# TUEV071.net
KiCad netlist of a schematic drawn in EAGLE
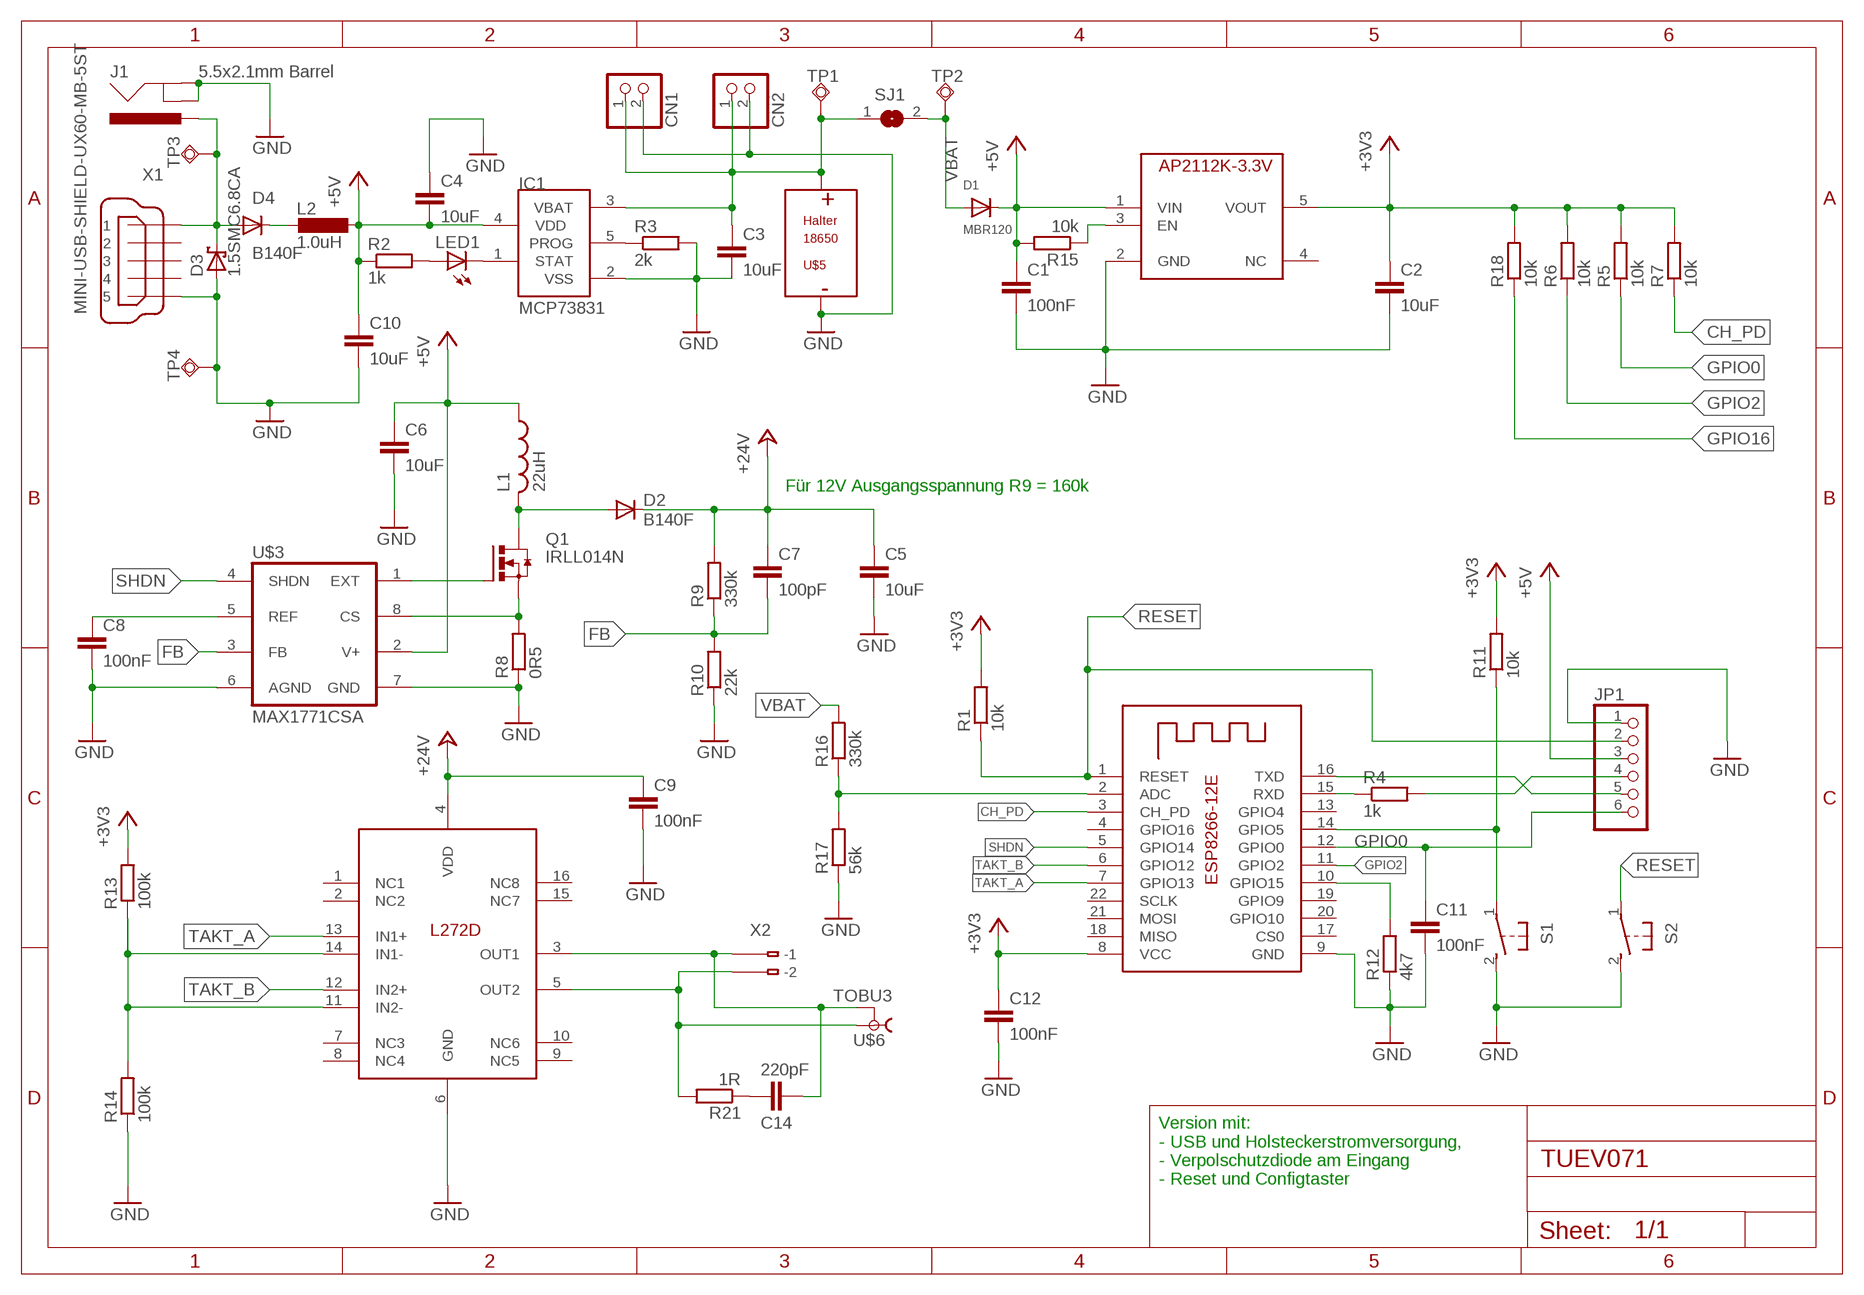
[diagram p0: schematic, sheet 1]

(export (version "E")
  (design (tool "Eeschema 10.0.6"))
  (components
    (comp (ref "C1")
      (value "100nF")
      (footprint "eagle-import:C0603K")
      (libsource (lib "eagle-import") (part "C-EUC0603K"))
    )
    (comp (ref "C2")
      (value "10uF")
      (footprint "eagle-import:C0603K")
      (libsource (lib "eagle-import") (part "C-EUC0603K"))
    )
    (comp (ref "C3")
      (value "10uF")
      (footprint "eagle-import:C0603K")
      (libsource (lib "eagle-import") (part "C-EUC0603K"))
    )
    (comp (ref "C4")
      (value "10uF")
      (footprint "eagle-import:C0603K")
      (libsource (lib "eagle-import") (part "C-EUC0603K"))
    )
    (comp (ref "C5")
      (value "10uF")
      (footprint "eagle-import:C1210K")
      (libsource (lib "eagle-import") (part "C-EUC1210K"))
    )
    (comp (ref "C6")
      (value "10uF")
      (footprint "eagle-import:C0603K")
      (libsource (lib "eagle-import") (part "C-EUC0603K"))
    )
    (comp (ref "C7")
      (value "100pF")
      (footprint "eagle-import:C0603K")
      (libsource (lib "eagle-import") (part "C-EUC0603K"))
    )
    (comp (ref "C8")
      (value "100nF")
      (footprint "eagle-import:C0603K")
      (libsource (lib "eagle-import") (part "C-EUC0603K"))
    )
    (comp (ref "C9")
      (value "100nF")
      (footprint "eagle-import:C0603K")
      (libsource (lib "eagle-import") (part "C-EUC0603K"))
    )
    (comp (ref "C10")
      (value "10uF")
      (footprint "eagle-import:C0603K")
      (libsource (lib "eagle-import") (part "C-EUC0603K"))
    )
    (comp (ref "C11")
      (value "100nF")
      (footprint "eagle-import:C0603K")
      (libsource (lib "eagle-import") (part "C-EUC0603K"))
    )
    (comp (ref "C12")
      (value "100nF")
      (footprint "eagle-import:C0603K")
      (libsource (lib "eagle-import") (part "C-EUC0603K"))
    )
    (comp (ref "C14")
      (value "220pF")
      (footprint "eagle-import:C0603K")
      (libsource (lib "eagle-import") (part "C-EUC0603K"))
    )
    (comp (ref "CN1")
      (value "JST_2PIN-SMT-RA")
      (footprint "eagle-import:JST-PH-2-SMT-RA")
      (libsource (lib "eagle-import") (part "JST_2PIN-SMT-RA"))
    )
    (comp (ref "CN2")
      (value "JST_2PIN-SMT-RA")
      (footprint "eagle-import:JST-PH-2-SMT-RA")
      (libsource (lib "eagle-import") (part "JST_2PIN-SMT-RA"))
    )
    (comp (ref "D1")
      (value "MBR120")
      (footprint "eagle-import:SOD-123")
      (libsource (lib "eagle-import") (part "DIODESOD-123"))
    )
    (comp (ref "D2")
      (value "B140F")
      (footprint "eagle-import:DO214AC")
      (libsource (lib "eagle-import") (part "DIODE-DO214AC"))
    )
    (comp (ref "D3")
      (value "1.5SMC6.8CA")
      (footprint "eagle-import:SMC")
      (libsource (lib "eagle-import") (part "SCHOTTKY-DIODESMC"))
    )
    (comp (ref "D4")
      (value "B140F")
      (footprint "eagle-import:DO214AC")
      (libsource (lib "eagle-import") (part "DIODE-DO214AC"))
    )
    (comp (ref "IC1")
      (value "MCP73831")
      (footprint "eagle-import:SOT23-5L")
      (libsource (lib "eagle-import") (part "MCP73831"))
    )
    (comp (ref "J1")
      (value "5.5x2.1mm Barrel")
      (footprint "eagle-import:POWER_JACK_SMD")
      (libsource (lib "eagle-import") (part "POWER_JACKSMD"))
    )
    (comp (ref "JP1")
      (value "PINHD-1X6")
      (footprint "eagle-import:1X06")
      (libsource (lib "eagle-import") (part "PINHD-1X6"))
    )
    (comp (ref "L1")
      (value "22uH")
      (footprint "eagle-import:L5650M")
      (libsource (lib "eagle-import") (part "L-USL5650M"))
    )
    (comp (ref "L2")
      (value "1.0uH")
      (footprint "eagle-import:L3230M")
      (libsource (lib "eagle-import") (part "L-EUL3230M"))
    )
    (comp (ref "LED1")
      (value "LEDCHIPLED_0805")
      (footprint "eagle-import:CHIPLED_0805")
      (libsource (lib "eagle-import") (part "LEDCHIPLED_0805"))
    )
    (comp (ref "Q1")
      (value "IRLL014N")
      (footprint "eagle-import:SOT223")
      (libsource (lib "eagle-import") (part "N-HEXFET-2D_?-SOT232IRLL014N"))
    )
    (comp (ref "R1")
      (value "10k")
      (footprint "eagle-import:M1206")
      (libsource (lib "eagle-import") (part "R-EU_M1206"))
    )
    (comp (ref "R2")
      (value "1k")
      (footprint "eagle-import:M1206")
      (libsource (lib "eagle-import") (part "R-EU_M1206"))
    )
    (comp (ref "R3")
      (value "2k")
      (footprint "eagle-import:M1206")
      (libsource (lib "eagle-import") (part "R-EU_M1206"))
    )
    (comp (ref "R4")
      (value "1k")
      (footprint "eagle-import:M1206")
      (libsource (lib "eagle-import") (part "R-EU_M1206"))
    )
    (comp (ref "R5")
      (value "10k")
      (footprint "eagle-import:M1206")
      (libsource (lib "eagle-import") (part "R-EU_M1206"))
    )
    (comp (ref "R6")
      (value "10k")
      (footprint "eagle-import:M1206")
      (libsource (lib "eagle-import") (part "R-EU_M1206"))
    )
    (comp (ref "R7")
      (value "10k")
      (footprint "eagle-import:M1206")
      (libsource (lib "eagle-import") (part "R-EU_M1206"))
    )
    (comp (ref "R8")
      (value "0R5")
      (footprint "eagle-import:R2512")
      (libsource (lib "eagle-import") (part "R-EU_R2512"))
    )
    (comp (ref "R9")
      (value "330k")
      (footprint "eagle-import:M1206")
      (libsource (lib "eagle-import") (part "R-EU_M1206"))
    )
    (comp (ref "R10")
      (value "22k")
      (footprint "eagle-import:M1206")
      (libsource (lib "eagle-import") (part "R-EU_M1206"))
    )
    (comp (ref "R11")
      (value "10k")
      (footprint "eagle-import:M1206")
      (libsource (lib "eagle-import") (part "R-EU_M1206"))
    )
    (comp (ref "R12")
      (value "4k7")
      (footprint "eagle-import:M1206")
      (libsource (lib "eagle-import") (part "R-EU_M1206"))
    )
    (comp (ref "R13")
      (value "100k")
      (footprint "eagle-import:M1206")
      (libsource (lib "eagle-import") (part "R-EU_M1206"))
    )
    (comp (ref "R14")
      (value "100k")
      (footprint "eagle-import:M1206")
      (libsource (lib "eagle-import") (part "R-EU_M1206"))
    )
    (comp (ref "R15")
      (value "10k")
      (footprint "eagle-import:M1206")
      (libsource (lib "eagle-import") (part "R-EU_M1206"))
    )
    (comp (ref "R16")
      (value "330k")
      (footprint "eagle-import:M1206")
      (libsource (lib "eagle-import") (part "R-EU_M1206"))
    )
    (comp (ref "R17")
      (value "56k")
      (footprint "eagle-import:M1206")
      (libsource (lib "eagle-import") (part "R-EU_M1206"))
    )
    (comp (ref "R18")
      (value "10k")
      (footprint "eagle-import:M1206")
      (libsource (lib "eagle-import") (part "R-EU_M1206"))
    )
    (comp (ref "R21")
      (value "1R")
      (footprint "eagle-import:M1206")
      (libsource (lib "eagle-import") (part "R-EU_M1206"))
    )
    (comp (ref "S1")
      (value "31-XX")
      (footprint "eagle-import:B3F-31XX")
      (fields (field (name "MPN") "B3F-3100"))
      (libsource (lib "eagle-import") (part "31-XX"))
    )
    (comp (ref "S2")
      (value "31-XX")
      (footprint "eagle-import:B3F-31XX")
      (fields (field (name "MPN") "B3F-3100"))
      (libsource (lib "eagle-import") (part "31-XX"))
    )
    (comp (ref "SJ1") (value "SJ") (footprint "eagle-import:SJ") (libsource (lib "eagle-import") (part "SJ")))
    (comp (ref "TP1")
      (value "TPSQPAD1-13Y")
      (footprint "eagle-import:P1-13Y")
      (libsource (lib "eagle-import") (part "TPSQPAD1-13Y"))
    )
    (comp (ref "TP2")
      (value "TPSQPAD1-13Y")
      (footprint "eagle-import:P1-13Y")
      (libsource (lib "eagle-import") (part "TPSQPAD1-13Y"))
    )
    (comp (ref "TP3")
      (value "TPSQPAD1-13Y")
      (footprint "eagle-import:P1-13Y")
      (libsource (lib "eagle-import") (part "TPSQPAD1-13Y"))
    )
    (comp (ref "TP4")
      (value "TPSQPAD1-13Y")
      (footprint "eagle-import:P1-13Y")
      (libsource (lib "eagle-import") (part "TPSQPAD1-13Y"))
    )
    (comp (ref "U$1")
      (value "AP2112-3.3")
      (footprint "eagle-import:SOT23-5L")
      (libsource (lib "eagle-import") (part "AP2112-3.3"))
    )
    (comp (ref "U$2")
      (value "L272D")
      (footprint "eagle-import:SO16")
      (libsource (lib "eagle-import") (part "L272D"))
    )
    (comp (ref "U$3")
      (value "MAX1771CSA")
      (footprint "eagle-import:SO08")
      (libsource (lib "eagle-import") (part "MAX1771CSA"))
    )
    (comp (ref "U$4")
      (value "ESP-12E")
      (footprint "eagle-import:ESP-12E")
      (libsource (lib "eagle-import") (part "ESP-12E"))
    )
    (comp (ref "U$5")
      (value "HA1X18650SMD")
      (footprint "eagle-import:HA1X18650SMD")
      (libsource (lib "eagle-import") (part "HA1X18650SMD"))
    )
    (comp (ref "U$6")
      (value "TOBU3")
      (footprint "eagle-import:TOBU3-REICHELT")
      (libsource (lib "eagle-import") (part "TOBU3-REICHELT"))
    )
    (comp (ref "X1")
      (value "MINI-USB-SHIELD-UX60-MB-5ST")
      (footprint "eagle-import:UX60-MB-5ST")
      (libsource (lib "eagle-import") (part "MINI-USB-SHIELD-UX60-MB-5ST"))
    )
    (comp (ref "X2")
      (value "233-102")
      (footprint "eagle-import:233-102")
      (libsource (lib "eagle-import") (part "233-102"))
    )
  )
  (nets
    (net (code "1") (name "+3V3") (class "Default")
      (node (ref "C12") (pin "1") (pinfunction "1_1") (pintype "passive"))
      (node (ref "C2") (pin "1") (pinfunction "1_1") (pintype "passive"))
      (node (ref "R1") (pin "2") (pinfunction "2_2") (pintype "passive"))
      (node (ref "R11") (pin "2") (pinfunction "2_2") (pintype "passive"))
      (node (ref "R13") (pin "2") (pinfunction "2_2") (pintype "passive"))
      (node (ref "R18") (pin "2") (pinfunction "2_2") (pintype "passive"))
      (node (ref "R5") (pin "2") (pinfunction "2_2") (pintype "passive"))
      (node (ref "R6") (pin "2") (pinfunction "2_2") (pintype "passive"))
      (node (ref "R7") (pin "2") (pinfunction "2_2") (pintype "passive"))
      (node (ref "U$1") (pin "5") (pinfunction "VOUT_5") (pintype "power_in"))
      (node (ref "U$4") (pin "8") (pinfunction "VCC_8") (pintype "power_in"))
    )
    (net (code "2") (name "+5V") (class "Default")
      (node (ref "C1") (pin "1") (pinfunction "1_1") (pintype "passive"))
      (node (ref "C10") (pin "1") (pinfunction "1_1") (pintype "passive"))
      (node (ref "C4") (pin "2") (pinfunction "2_2") (pintype "passive"))
      (node (ref "C6") (pin "1") (pinfunction "1_1") (pintype "passive"))
      (node (ref "D1") (pin "C") (pinfunction "C_C") (pintype "passive"))
      (node (ref "IC1") (pin "4") (pinfunction "VDD_4") (pintype "bidirectional"))
      (node (ref "JP1") (pin "3") (pinfunction "3_3") (pintype "passive"))
      (node (ref "L1") (pin "1") (pinfunction "1_1") (pintype "passive"))
      (node (ref "L2") (pin "1") (pinfunction "1_1") (pintype "passive"))
      (node (ref "R15") (pin "2") (pinfunction "2_2") (pintype "passive"))
      (node (ref "R2") (pin "1") (pinfunction "1_1") (pintype "passive"))
      (node (ref "U$1") (pin "1") (pinfunction "VIN_1") (pintype "power_in"))
      (node (ref "U$3") (pin "2") (pinfunction "V+_2") (pintype "power_in"))
    )
    (net (code "3") (name "+24V") (class "Default")
      (node (ref "C5") (pin "1") (pinfunction "1_1") (pintype "passive"))
      (node (ref "C7") (pin "1") (pinfunction "1_1") (pintype "passive"))
      (node (ref "C9") (pin "1") (pinfunction "1_1") (pintype "passive"))
      (node (ref "D2") (pin "C") (pinfunction "C_C") (pintype "passive"))
      (node (ref "R9") (pin "2") (pinfunction "2_2") (pintype "passive"))
      (node (ref "U$2") (pin "4") (pinfunction "VDD_4") (pintype "power_in"))
    )
    (net (code "4") (name "CH_PD") (class "Default")
      (node (ref "R7") (pin "1") (pinfunction "1_1") (pintype "passive"))
      (node (ref "U$4") (pin "3") (pinfunction "CH_PD_3") (pintype "input"))
    )
    (net (code "5") (name "FB") (class "Default")
      (node (ref "C7") (pin "2") (pinfunction "2_2") (pintype "passive"))
      (node (ref "R10") (pin "2") (pinfunction "2_2") (pintype "passive"))
      (node (ref "R9") (pin "1") (pinfunction "1_1") (pintype "passive"))
      (node (ref "U$3") (pin "3") (pinfunction "FB_3") (pintype "input"))
    )
    (net (code "6") (name "GND") (class "Default")
      (node (ref "C1") (pin "2") (pinfunction "2_2") (pintype "passive"))
      (node (ref "C10") (pin "2") (pinfunction "2_2") (pintype "passive"))
      (node (ref "C11") (pin "2") (pinfunction "2_2") (pintype "passive"))
      (node (ref "C12") (pin "2") (pinfunction "2_2") (pintype "passive"))
      (node (ref "C2") (pin "2") (pinfunction "2_2") (pintype "passive"))
      (node (ref "C3") (pin "2") (pinfunction "2_2") (pintype "passive"))
      (node (ref "C4") (pin "1") (pinfunction "1_1") (pintype "passive"))
      (node (ref "C5") (pin "2") (pinfunction "2_2") (pintype "passive"))
      (node (ref "C6") (pin "2") (pinfunction "2_2") (pintype "passive"))
      (node (ref "C8") (pin "2") (pinfunction "2_2") (pintype "passive"))
      (node (ref "C9") (pin "2") (pinfunction "2_2") (pintype "passive"))
      (node (ref "CN1") (pin "2") (pinfunction "1_2") (pintype "passive"))
      (node (ref "CN2") (pin "2") (pinfunction "1_2") (pintype "passive"))
      (node (ref "D3") (pin "A") (pinfunction "A_A") (pintype "passive"))
      (node (ref "IC1") (pin "2") (pinfunction "VSS_2") (pintype "bidirectional"))
      (node (ref "J1") (pin "GND") (pinfunction "GNDBREAK_GND") (pintype "bidirectional"))
      (node (ref "J1") (pin "P$4") (pinfunction "GND_P$4") (pintype "bidirectional"))
      (node (ref "JP1") (pin "1") (pinfunction "1_1") (pintype "passive"))
      (node (ref "R10") (pin "1") (pinfunction "1_1") (pintype "passive"))
      (node (ref "R12") (pin "1") (pinfunction "1_1") (pintype "passive"))
      (node (ref "R14") (pin "1") (pinfunction "1_1") (pintype "passive"))
      (node (ref "R17") (pin "1") (pinfunction "1_1") (pintype "passive"))
      (node (ref "R3") (pin "2") (pinfunction "2_2") (pintype "passive"))
      (node (ref "R8") (pin "1") (pinfunction "1_1") (pintype "passive"))
      (node (ref "S1") (pin "2") (pinfunction "S_2") (pintype "passive"))
      (node (ref "S2") (pin "2") (pinfunction "S_2") (pintype "passive"))
      (node (ref "TP4") (pin "TP") (pinfunction "TP_TP") (pintype "input"))
      (node (ref "U$1") (pin "2") (pinfunction "GND_2") (pintype "power_in"))
      (node (ref "U$2") (pin "6") (pinfunction "GND_6") (pintype "power_in"))
      (node (ref "U$3") (pin "6") (pinfunction "AGND_6") (pintype "input"))
      (node (ref "U$3") (pin "7") (pinfunction "GND_7") (pintype "power_in"))
      (node (ref "U$4") (pin "9") (pinfunction "GND_9") (pintype "power_in"))
      (node (ref "U$5") (pin "P$2-") (pinfunction "P$2-_P$2-") (pintype "bidirectional"))
      (node (ref "X1") (pin "5") (pinfunction "5_5") (pintype "input"))
    )
    (net (code "7") (name "GPIO0") (class "Default")
      (node (ref "C11") (pin "1") (pinfunction "1_1") (pintype "passive"))
      (node (ref "JP1") (pin "6") (pinfunction "6_6") (pintype "passive"))
      (node (ref "R5") (pin "1") (pinfunction "1_1") (pintype "passive"))
      (node (ref "U$4") (pin "12") (pinfunction "GPIO0_12") (pintype "bidirectional"))
    )
    (net (code "8") (name "GPIO2") (class "Default")
      (node (ref "R6") (pin "1") (pinfunction "1_1") (pintype "passive"))
      (node (ref "U$4") (pin "11") (pinfunction "GPIO2_11") (pintype "bidirectional"))
    )
    (net (code "9") (name "GPIO16") (class "Default")
      (node (ref "R18") (pin "1") (pinfunction "1_1") (pintype "passive"))
    )
    (net (code "10") (name "Net-(C14-Pad1)") (class "Default")
      (node (ref "C14") (pin "1") (pinfunction "1_1") (pintype "passive"))
      (node (ref "R21") (pin "1") (pinfunction "1_1") (pintype "passive"))
    )
    (net (code "11") (name "Net-(CN1-2)") (class "Default")
      (node (ref "C3") (pin "1") (pinfunction "1_1") (pintype "passive"))
      (node (ref "CN1") (pin "1") (pinfunction "2_1") (pintype "passive"))
      (node (ref "CN2") (pin "1") (pinfunction "2_1") (pintype "passive"))
      (node (ref "IC1") (pin "3") (pinfunction "VBAT_3") (pintype "bidirectional"))
      (node (ref "SJ1") (pin "1") (pinfunction "1_1") (pintype "passive"))
      (node (ref "TP1") (pin "TP") (pinfunction "TP_TP") (pintype "input"))
      (node (ref "U$5") (pin "P$1+") (pinfunction "P$1+_P$1+") (pintype "bidirectional"))
    )
    (net (code "12") (name "Net-(D2-PadA)") (class "Default")
      (node (ref "D2") (pin "A") (pinfunction "A_A") (pintype "passive"))
      (node (ref "L1") (pin "2") (pinfunction "2_2") (pintype "passive"))
      (node (ref "Q1") (pin "2") (pinfunction "D_2") (pintype "passive"))
      (node (ref "Q1") (pin "4") (pinfunction "D_4") (pintype "passive"))
    )
    (net (code "13") (name "Net-(D4-PadC)") (class "Default")
      (node (ref "D4") (pin "C") (pinfunction "C_C") (pintype "passive"))
      (node (ref "L2") (pin "2") (pinfunction "2_2") (pintype "passive"))
    )
    (net (code "14") (name "Net-(IC1-PROG)") (class "Default")
      (node (ref "IC1") (pin "5") (pinfunction "PROG_5") (pintype "bidirectional"))
      (node (ref "R3") (pin "1") (pinfunction "1_1") (pintype "passive"))
    )
    (net (code "15") (name "Net-(IC1-STAT)") (class "Default")
      (node (ref "IC1") (pin "1") (pinfunction "STAT_1") (pintype "bidirectional"))
      (node (ref "LED1") (pin "C") (pinfunction "C_C") (pintype "passive"))
    )
    (net (code "16") (name "Net-(J1-PWR)") (class "Default")
      (node (ref "D3") (pin "C") (pinfunction "C_C") (pintype "passive"))
      (node (ref "D4") (pin "A") (pinfunction "A_A") (pintype "passive"))
      (node (ref "J1") (pin "VIN0") (pinfunction "PWR_VIN0") (pintype "bidirectional"))
      (node (ref "TP3") (pin "TP") (pinfunction "TP_TP") (pintype "input"))
      (node (ref "X1") (pin "1") (pinfunction "1_1") (pintype "input"))
    )
    (net (code "17") (name "Net-(JP1-Pad4)") (class "Default")
      (node (ref "JP1") (pin "4") (pinfunction "4_4") (pintype "passive"))
      (node (ref "R4") (pin "2") (pinfunction "2_2") (pintype "passive"))
    )
    (net (code "18") (name "Net-(LED1-PadA)") (class "Default")
      (node (ref "LED1") (pin "A") (pinfunction "A_A") (pintype "passive"))
      (node (ref "R2") (pin "2") (pinfunction "2_2") (pintype "passive"))
    )
    (net (code "19") (name "Net-(Q1-G)") (class "Default")
      (node (ref "Q1") (pin "1") (pinfunction "G_1") (pintype "passive"))
      (node (ref "U$3") (pin "1") (pinfunction "EXT_1") (pintype "output"))
    )
    (net (code "20") (name "Net-(Q1-S)") (class "Default")
      (node (ref "Q1") (pin "3") (pinfunction "S_3") (pintype "passive"))
      (node (ref "R8") (pin "2") (pinfunction "2_2") (pintype "passive"))
      (node (ref "U$3") (pin "8") (pinfunction "CS_8") (pintype "input"))
    )
    (net (code "21") (name "Net-(S1-P)") (class "Default")
      (node (ref "R11") (pin "1") (pinfunction "1_1") (pintype "passive"))
      (node (ref "S1") (pin "1") (pinfunction "P_1") (pintype "passive"))
      (node (ref "U$4") (pin "14") (pinfunction "GPIO5_14") (pintype "bidirectional"))
    )
    (net (code "22") (name "Net-(U$1-EN)") (class "Default")
      (node (ref "R15") (pin "1") (pinfunction "1_1") (pintype "passive"))
      (node (ref "U$1") (pin "3") (pinfunction "EN_3") (pintype "input"))
    )
    (net (code "23") (name "Net-(U$2-IN1-)") (class "Default")
      (node (ref "R13") (pin "1") (pinfunction "1_1") (pintype "passive"))
      (node (ref "R14") (pin "2") (pinfunction "2_2") (pintype "passive"))
      (node (ref "U$2") (pin "11") (pinfunction "IN2-_11") (pintype "bidirectional"))
      (node (ref "U$2") (pin "14") (pinfunction "IN1-_14") (pintype "bidirectional"))
    )
    (net (code "24") (name "Net-(U$2-OUT1)") (class "Default")
      (node (ref "C14") (pin "2") (pinfunction "2_2") (pintype "passive"))
      (node (ref "U$2") (pin "3") (pinfunction "OUT1_3") (pintype "output"))
      (node (ref "U$6") (pin "2") (pinfunction "2_2") (pintype "passive"))
      (node (ref "U$6") (pin "2@1") (pinfunction "2_2@1") (pintype "passive"))
      (node (ref "U$6") (pin "2@2") (pinfunction "2_2@2") (pintype "passive"))
      (node (ref "X2") (pin "B1") (pinfunction "B-1_B1") (pintype "passive"))
    )
    (net (code "25") (name "Net-(U$2-OUT2)") (class "Default")
      (node (ref "R21") (pin "2") (pinfunction "2_2") (pintype "passive"))
      (node (ref "U$2") (pin "5") (pinfunction "OUT2_5") (pintype "output"))
      (node (ref "U$6") (pin "1") (pinfunction "1_1") (pintype "passive"))
      (node (ref "X2") (pin "B2") (pinfunction "B-2_B2") (pintype "passive"))
    )
    (net (code "26") (name "Net-(U$3-REF)") (class "Default")
      (node (ref "C8") (pin "1") (pinfunction "1_1") (pintype "passive"))
      (node (ref "U$3") (pin "5") (pinfunction "REF_5") (pintype "input"))
    )
    (net (code "27") (name "Net-(U$4-ADC)") (class "Default")
      (node (ref "R16") (pin "1") (pinfunction "1_1") (pintype "passive"))
      (node (ref "R17") (pin "2") (pinfunction "2_2") (pintype "passive"))
      (node (ref "U$4") (pin "2") (pinfunction "ADC_2") (pintype "passive"))
    )
    (net (code "28") (name "Net-(U$4-GPIO15)") (class "Default")
      (node (ref "R12") (pin "2") (pinfunction "2_2") (pintype "passive"))
      (node (ref "U$4") (pin "10") (pinfunction "GPIO15_10") (pintype "bidirectional"))
    )
    (net (code "29") (name "Net-(U$4-RXD)") (class "Default")
      (node (ref "R4") (pin "1") (pinfunction "1_1") (pintype "passive"))
      (node (ref "U$4") (pin "15") (pinfunction "RXD_15") (pintype "input"))
    )
    (net (code "30") (name "Net-(U$4-TXD)") (class "Default")
      (node (ref "JP1") (pin "5") (pinfunction "5_5") (pintype "passive"))
      (node (ref "U$4") (pin "16") (pinfunction "TXD_16") (pintype "output"))
    )
    (net (code "31") (name "RESET") (class "Default")
      (node (ref "JP1") (pin "2") (pinfunction "2_2") (pintype "passive"))
      (node (ref "R1") (pin "1") (pinfunction "1_1") (pintype "passive"))
      (node (ref "S2") (pin "1") (pinfunction "P_1") (pintype "passive"))
      (node (ref "U$4") (pin "1") (pinfunction "RESET_1") (pintype "input"))
    )
    (net (code "32") (name "SHDN") (class "Default")
      (node (ref "U$3") (pin "4") (pinfunction "SHDN_4") (pintype "input"))
      (node (ref "U$4") (pin "5") (pinfunction "GPIO14_5") (pintype "bidirectional"))
    )
    (net (code "33") (name "TAKT_A") (class "Default")
      (node (ref "U$2") (pin "13") (pinfunction "IN1+_13") (pintype "input"))
      (node (ref "U$4") (pin "7") (pinfunction "GPIO13_7") (pintype "bidirectional"))
    )
    (net (code "34") (name "TAKT_B") (class "Default")
      (node (ref "U$2") (pin "12") (pinfunction "IN2+_12") (pintype "bidirectional"))
      (node (ref "U$4") (pin "6") (pinfunction "GPIO12_6") (pintype "bidirectional"))
    )
    (net (code "35") (name "VBAT") (class "Default")
      (node (ref "D1") (pin "A") (pinfunction "A_A") (pintype "passive"))
      (node (ref "R16") (pin "2") (pinfunction "2_2") (pintype "passive"))
      (node (ref "SJ1") (pin "2") (pinfunction "2_2") (pintype "passive"))
      (node (ref "TP2") (pin "TP") (pinfunction "TP_TP") (pintype "input"))
    )
    (net (code "36") (name "unconnected-(U$1-NC-Pad4)") (class "Default")
      (node (ref "U$1") (pin "4") (pinfunction "NC_4") (pintype "no_connect"))
    )
    (net (code "37") (name "unconnected-(U$2-NC1-Pad1)") (class "Default")
      (node (ref "U$2") (pin "1") (pinfunction "NC1_1") (pintype "no_connect"))
    )
    (net (code "38") (name "unconnected-(U$2-NC2-Pad2)") (class "Default")
      (node (ref "U$2") (pin "2") (pinfunction "NC2_2") (pintype "bidirectional"))
    )
    (net (code "39") (name "unconnected-(U$2-NC3-Pad7)") (class "Default")
      (node (ref "U$2") (pin "7") (pinfunction "NC3_7") (pintype "bidirectional"))
    )
    (net (code "40") (name "unconnected-(U$2-NC4-Pad8)") (class "Default")
      (node (ref "U$2") (pin "8") (pinfunction "NC4_8") (pintype "bidirectional"))
    )
    (net (code "41") (name "unconnected-(U$2-NC5-Pad9)") (class "Default")
      (node (ref "U$2") (pin "9") (pinfunction "NC5_9") (pintype "bidirectional"))
    )
    (net (code "42") (name "unconnected-(U$2-NC6-Pad10)") (class "Default")
      (node (ref "U$2") (pin "10") (pinfunction "NC6_10") (pintype "bidirectional"))
    )
    (net (code "43") (name "unconnected-(U$2-NC7-Pad15)") (class "Default")
      (node (ref "U$2") (pin "15") (pinfunction "NC7_15") (pintype "bidirectional"))
    )
    (net (code "44") (name "unconnected-(U$2-NC8-Pad16)") (class "Default")
      (node (ref "U$2") (pin "16") (pinfunction "NC8_16") (pintype "bidirectional"))
    )
    (net (code "45") (name "unconnected-(U$4-CS0-Pad17)") (class "Default")
      (node (ref "U$4") (pin "17") (pinfunction "CS0_17") (pintype "bidirectional"))
    )
    (net (code "46") (name "unconnected-(U$4-GPIO4-Pad13)") (class "Default")
      (node (ref "U$4") (pin "13") (pinfunction "GPIO4_13") (pintype "bidirectional"))
    )
    (net (code "47") (name "unconnected-(U$4-GPIO9-Pad19)") (class "Default")
      (node (ref "U$4") (pin "19") (pinfunction "GPIO9_19") (pintype "bidirectional"))
    )
    (net (code "48") (name "unconnected-(U$4-GPIO10-Pad20)") (class "Default")
      (node (ref "U$4") (pin "20") (pinfunction "GPIO10_20") (pintype "bidirectional"))
    )
    (net (code "49") (name "unconnected-(U$4-GPIO16-Pad4)") (class "Default")
      (node (ref "U$4") (pin "4") (pinfunction "GPIO16_4") (pintype "bidirectional"))
    )
    (net (code "50") (name "unconnected-(U$4-MISO-Pad18)") (class "Default")
      (node (ref "U$4") (pin "18") (pinfunction "MISO_18") (pintype "bidirectional"))
    )
    (net (code "51") (name "unconnected-(U$4-MOSI-Pad21)") (class "Default")
      (node (ref "U$4") (pin "21") (pinfunction "MOSI_21") (pintype "bidirectional"))
    )
    (net (code "52") (name "unconnected-(U$4-SCLK-Pad22)") (class "Default")
      (node (ref "U$4") (pin "22") (pinfunction "SCLK_22") (pintype "bidirectional"))
    )
    (net (code "53") (name "unconnected-(X1-Pad2)") (class "Default")
      (node (ref "X1") (pin "2") (pinfunction "2_2") (pintype "input"))
    )
    (net (code "54") (name "unconnected-(X1-Pad3)") (class "Default")
      (node (ref "X1") (pin "3") (pinfunction "3_3") (pintype "input"))
    )
    (net (code "55") (name "unconnected-(X1-Pad4)") (class "Default")
      (node (ref "X1") (pin "4") (pinfunction "4_4") (pintype "input"))
    )
    (net (code "56") (name "unconnected-(X2--1-PadA1)") (class "Default")
      (node (ref "X2") (pin "A1") (pinfunction "-1_A1") (pintype "passive"))
    )
    (net (code "57") (name "unconnected-(X2--2-PadA2)") (class "Default")
      (node (ref "X2") (pin "A2") (pinfunction "-2_A2") (pintype "passive"))
    )
  )
)
